# MPU_Schem.net
KiCad netlist of a schematic drawn in Altium Designer
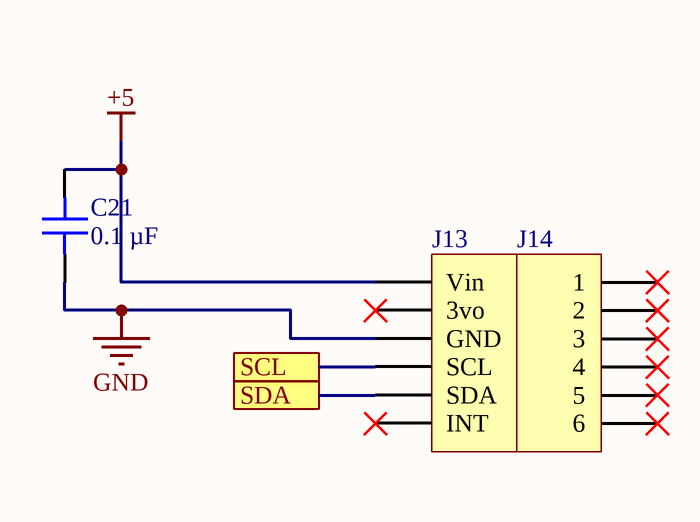
[diagram p0: MPU_Schem.SchDoc]

(export (version "E")
  (design (tool "Eeschema 10.0.6"))
  (components
    (comp (ref "C21")
      (value "0.1 µF")
      (footprint "CAP 1206_3216 - 0.8MM")
      (description "CAP CER 0.1UF 50V Y5V 1206")
      (fields (field (name "PART NUMBER") "CC1206ZRY5V9BB104") (field (name "MANUFACTURER") "Yageo"))
      (libsource (lib "Celestial Altium Library - altium_library") (part "Capacitor"))
    )
    (comp (ref "J13")
      (value "~")
      (footprint "HDR1X6")
      (description "Header, 6-Pin")
      (fields (field (name "PUBLISHER") "Altium Limited"))
      (libsource (lib "Miscellaneous Connectors") (part "Header 6"))
    )
    (comp (ref "J14")
      (value "~")
      (footprint "HDR1X6")
      (description "Header, 6-Pin")
      (fields (field (name "PUBLISHER") "Altium Limited"))
      (libsource (lib "") (part "Header 6_1"))
    )
  )
  (nets
    (net (code "1") (name "+5") (class "Default")
      (node (ref "C21") (pin "2") (pinfunction "2_2") (pintype "passive"))
      (node (ref "J13") (pin "1") (pinfunction "Vin_1") (pintype "passive"))
    )
    (net (code "2") (name "/SCL") (class "Default")
      (node (ref "J13") (pin "4") (pinfunction "SCL_4") (pintype "passive"))
    )
    (net (code "3") (name "/SDA") (class "Default")
      (node (ref "J13") (pin "5") (pinfunction "SDA_5") (pintype "passive"))
    )
    (net (code "4") (name "GND") (class "Default")
      (node (ref "C21") (pin "1") (pinfunction "1_1") (pintype "passive"))
      (node (ref "J13") (pin "3") (pinfunction "GND_3") (pintype "passive"))
    )
    (net (code "5") (name "unconnected-(J13-3vo-Pad2)") (class "Default")
      (node (ref "J13") (pin "2") (pinfunction "3vo_2") (pintype "passive+no_connect"))
    )
    (net (code "6") (name "unconnected-(J13-INT-Pad6)") (class "Default")
      (node (ref "J13") (pin "6") (pinfunction "INT_6") (pintype "passive+no_connect"))
    )
    (net (code "7") (name "unconnected-(J14-Pad1)") (class "Default")
      (node (ref "J14") (pin "1") (pinfunction "1_1") (pintype "passive+no_connect"))
    )
    (net (code "8") (name "unconnected-(J14-Pad2)") (class "Default")
      (node (ref "J14") (pin "2") (pinfunction "2_2") (pintype "passive+no_connect"))
    )
    (net (code "9") (name "unconnected-(J14-Pad3)") (class "Default")
      (node (ref "J14") (pin "3") (pinfunction "3_3") (pintype "passive+no_connect"))
    )
    (net (code "10") (name "unconnected-(J14-Pad4)") (class "Default")
      (node (ref "J14") (pin "4") (pinfunction "4_4") (pintype "passive+no_connect"))
    )
    (net (code "11") (name "unconnected-(J14-Pad5)") (class "Default")
      (node (ref "J14") (pin "5") (pinfunction "5_5") (pintype "passive+no_connect"))
    )
    (net (code "12") (name "unconnected-(J14-Pad6)") (class "Default")
      (node (ref "J14") (pin "6") (pinfunction "6_6") (pintype "passive+no_connect"))
    )
  )
)
